# External_Stepper.net
KiCad netlist of a schematic drawn in Altium Designer
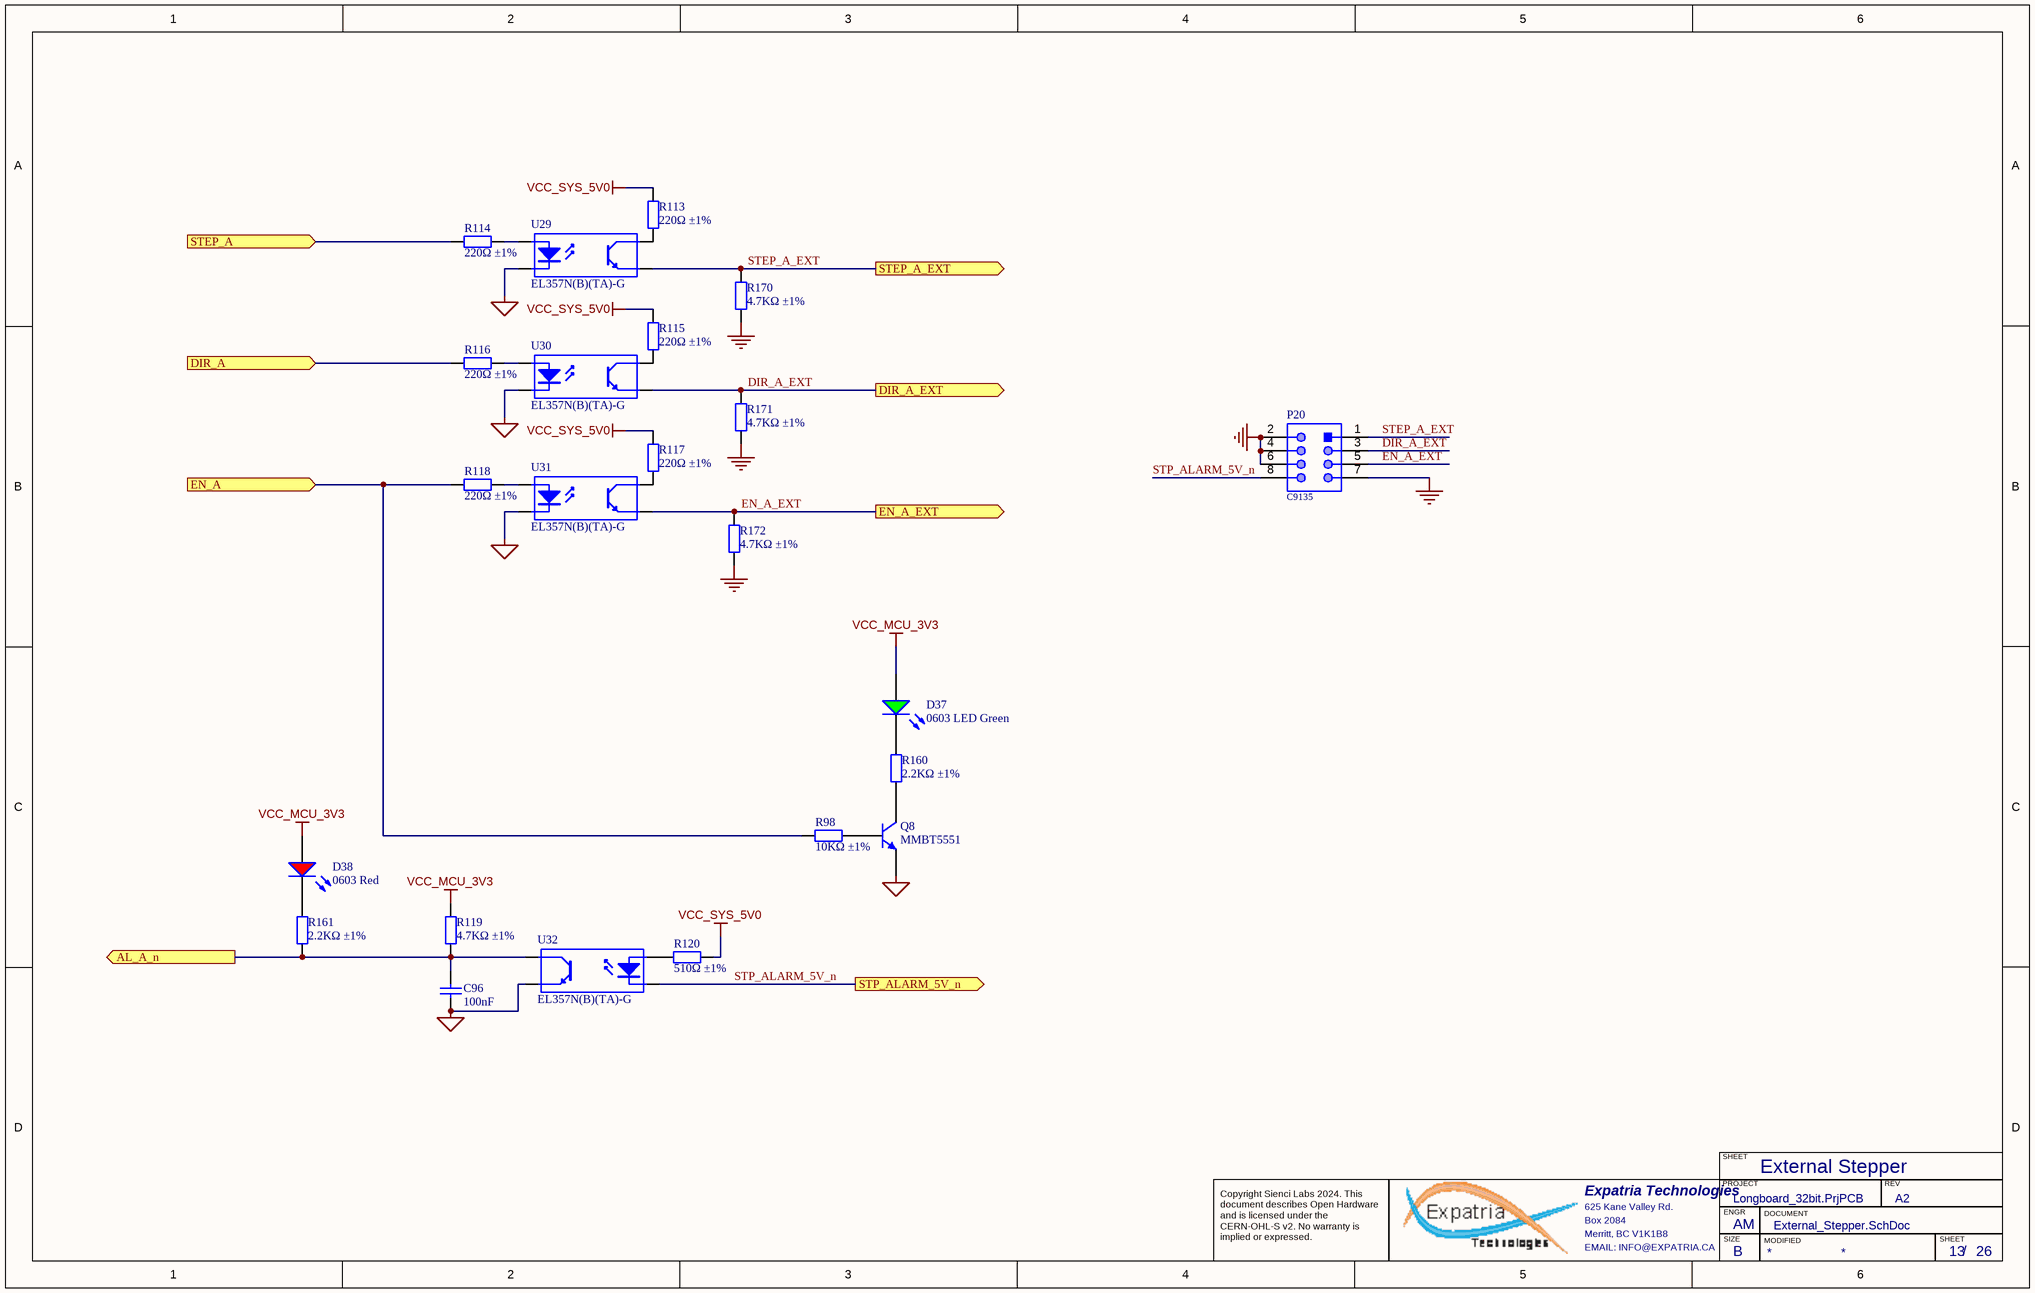
[diagram p0: External_Stepper.SchDoc]

(export (version "E")
  (design (tool "Eeschema 10.0.6"))
  (components
    (comp (ref "C96")
      (value "100nF")
      (footprint "0402_C")
      (description "16V 100nF X7R ±10% 0402 Multilayer Ceramic Capacitors MLCC - SMD/SMT ROHS")
      (fields (field (name "MANUFACTURER") "Samsung Electro-Mechanics") (field (name "TOLERANCE") "10%"))
      (libsource (lib "Sienci_Labs") (part "0402 100nF (104) 10% 16V"))
    )
    (comp (ref "D37")
      (value "0603 LED Green")
      (footprint "0603_LED_S1 - GREEN")
      (fields
        (field (name "MANUFACTURER PART NUMBER") "19-217/GHC-YR1S2/3T")
        (field (name "MANUFACTURER") "Everlight Elec")
      )
      (libsource (lib "Sienci_Labs") (part "19-217/GHC-YR1S2/3T"))
    )
    (comp (ref "D38")
      (value "0603 Red")
      (footprint "0603_LED_S1")
      (fields
        (field (name "MANUFACTURER") "Everlight Elec")
        (field (name "MANUFACTURER PART NUMBER") "19-213SURC/S530-A3/TR8")
      )
      (libsource (lib "Sienci_Labs") (part "19-213SURC/S530-A3/TR8"))
    )
    (comp (ref "P20")
      (value "C9135")
      (footprint "61200821621")
      (description "Male Box Header WR-BHD, THT, Vertical, pitch 2.54 mm, 8 pins")
      (fields
        (field (name "MANUFACTURER") "Wurth Electronics")
        (field (name "MANUFACTURER PART NUMBER") "61200821621")
        (field (name "PUBLISHER") "WurthElektronik")
      )
      (libsource (lib "Sienci_Labs") (part "HDR2x4P"))
    )
    (comp (ref "Q8")
      (value "MMBT5551")
      (footprint "SOT-23(SOT-23-3)")
      (fields (field (name "MANUFACTURER") "Jiangsu Changjing Electronics Technology"))
      (libsource (lib "Sienci_Labs") (part "MMBT5551"))
    )
    (comp (ref "R98")
      (value "10KΩ ±1%")
      (footprint "0603_R")
      (description "Chip resistor")
      (fields
        (field (name "MANUFACTURER") "Uniroyal Elec")
        (field (name "MANUFACTURER PART NUMBER") "0603WAF1002T5E")
      )
      (libsource (lib "RES") (part "0603 10K (1002) 1%"))
    )
    (comp (ref "R113")
      (value "220Ω ±1%")
      (footprint "0402_R")
      (description "Chip resistor")
      (fields
        (field (name "MANUFACTURER") "Uniroyal Elec")
        (field (name "MANUFACTURER PART NUMBER") "0402WGF2200TCE")
      )
      (libsource (lib "") (part "0402 220R (2200) 1%_1"))
    )
    (comp (ref "R114")
      (value "220Ω ±1%")
      (footprint "0402_R")
      (description "Chip resistor")
      (fields
        (field (name "MANUFACTURER") "Uniroyal Elec")
        (field (name "MANUFACTURER PART NUMBER") "0402WGF2200TCE")
      )
      (libsource (lib "RES") (part "0402 220R (2200) 1%"))
    )
    (comp (ref "R115")
      (value "220Ω ±1%")
      (footprint "0402_R")
      (description "Chip resistor")
      (fields
        (field (name "MANUFACTURER") "Uniroyal Elec")
        (field (name "MANUFACTURER PART NUMBER") "0402WGF2200TCE")
      )
      (libsource (lib "") (part "0402 220R (2200) 1%_1"))
    )
    (comp (ref "R116")
      (value "220Ω ±1%")
      (footprint "0402_R")
      (description "Chip resistor")
      (fields
        (field (name "MANUFACTURER") "Uniroyal Elec")
        (field (name "MANUFACTURER PART NUMBER") "0402WGF2200TCE")
      )
      (libsource (lib "RES") (part "0402 220R (2200) 1%"))
    )
    (comp (ref "R117")
      (value "220Ω ±1%")
      (footprint "0402_R")
      (description "Chip resistor")
      (fields
        (field (name "MANUFACTURER") "Uniroyal Elec")
        (field (name "MANUFACTURER PART NUMBER") "0402WGF2200TCE")
      )
      (libsource (lib "") (part "0402 220R (2200) 1%_1"))
    )
    (comp (ref "R118")
      (value "220Ω ±1%")
      (footprint "0402_R")
      (description "Chip resistor")
      (fields
        (field (name "MANUFACTURER") "Uniroyal Elec")
        (field (name "MANUFACTURER PART NUMBER") "0402WGF2200TCE")
      )
      (libsource (lib "RES") (part "0402 220R (2200) 1%"))
    )
    (comp (ref "R119")
      (value "4.7KΩ ±1%")
      (footprint "0402_R")
      (description "Chip resistor")
      (fields
        (field (name "MANUFACTURER") "Uniroyal Elec")
        (field (name "MANUFACTURER PART NUMBER") "0402WGF4701TCE")
      )
      (libsource (lib "") (part "0402 4.7K (4701) 1%_1"))
    )
    (comp (ref "R120")
      (value "510Ω ±1%")
      (footprint "0402_R")
      (description "Chip resistor")
      (fields
        (field (name "MANUFACTURER") "Uniroyal Elec")
        (field (name "MANUFACTURER PART NUMBER") "0402WGF5100TCE")
      )
      (libsource (lib "RES") (part "0402 510R (5100) 1%"))
    )
    (comp (ref "R160")
      (value "2.2KΩ ±1%")
      (footprint "0402_R")
      (description "Chip resistor")
      (fields
        (field (name "MANUFACTURER") "Uniroyal Elec")
        (field (name "MANUFACTURER PART NUMBER") "0402WGF2201TCE")
      )
      (libsource (lib "RES") (part "0402 2.2K (2201) 1%"))
    )
    (comp (ref "R161")
      (value "2.2KΩ ±1%")
      (footprint "0402_R")
      (description "Chip resistor")
      (fields
        (field (name "MANUFACTURER") "Uniroyal Elec")
        (field (name "MANUFACTURER PART NUMBER") "0402WGF2201TCE")
      )
      (libsource (lib "RES") (part "0402 2.2K (2201) 1%"))
    )
    (comp (ref "R170")
      (value "4.7KΩ ±1%")
      (footprint "0402_R")
      (description "Chip resistor")
      (fields
        (field (name "MANUFACTURER") "Uniroyal Elec")
        (field (name "MANUFACTURER PART NUMBER") "0402WGF4701TCE")
      )
      (libsource (lib "RES") (part "0402 4.7K (4701) 1%"))
    )
    (comp (ref "R171")
      (value "4.7KΩ ±1%")
      (footprint "0402_R")
      (description "Chip resistor")
      (fields
        (field (name "MANUFACTURER") "Uniroyal Elec")
        (field (name "MANUFACTURER PART NUMBER") "0402WGF4701TCE")
      )
      (libsource (lib "RES") (part "0402 4.7K (4701) 1%"))
    )
    (comp (ref "R172")
      (value "4.7KΩ ±1%")
      (footprint "0402_R")
      (description "Chip resistor")
      (fields
        (field (name "MANUFACTURER") "Uniroyal Elec")
        (field (name "MANUFACTURER PART NUMBER") "0402WGF4701TCE")
      )
      (libsource (lib "RES") (part "0402 4.7K (4701) 1%"))
    )
    (comp (ref "U29")
      (value "EL357N(B)(TA)-G")
      (footprint "Miscellaneous Devices LC:SOP-4_P2.54")
      (description "80V 3750V 50mA 0.1V@1mA,20mA 1 6V 1.2V DC SOP-4-2.54mm Optocouplers - Phototransistor Output ROHS")
      (fields (field (name "MANUFACTURER") "Everlight Elec"))
      (libsource (lib "IC") (part "EL357N(B)(TA)-G_[C6649]"))
    )
    (comp (ref "U30")
      (value "EL357N(B)(TA)-G")
      (footprint "Miscellaneous Devices LC:SOP-4_P2.54")
      (description "80V 3750V 50mA 0.1V@1mA,20mA 1 6V 1.2V DC SOP-4-2.54mm Optocouplers - Phototransistor Output ROHS")
      (fields (field (name "MANUFACTURER") "Everlight Elec"))
      (libsource (lib "IC") (part "EL357N(B)(TA)-G_[C6649]"))
    )
    (comp (ref "U31")
      (value "EL357N(B)(TA)-G")
      (footprint "Miscellaneous Devices LC:SOP-4_P2.54")
      (description "80V 3750V 50mA 0.1V@1mA,20mA 1 6V 1.2V DC SOP-4-2.54mm Optocouplers - Phototransistor Output ROHS")
      (fields (field (name "MANUFACTURER") "Everlight Elec"))
      (libsource (lib "IC") (part "EL357N(B)(TA)-G_[C6649]"))
    )
    (comp (ref "U32")
      (value "EL357N(B)(TA)-G")
      (footprint "Miscellaneous Devices LC:SOP-4_P2.54")
      (description "80V 3750V 50mA 0.1V@1mA,20mA 1 6V 1.2V DC SOP-4-2.54mm Optocouplers - Phototransistor Output ROHS")
      (fields (field (name "MANUFACTURER") "Everlight Elec"))
      (libsource (lib "IC") (part "EL357N(B)(TA)-G_[C6649]"))
    )
  )
  (nets
    (net (code "1") (name "/AL_A_n") (class "Default")
      (node (ref "C96") (pin "2") (pinfunction "2_2") (pintype "passive"))
      (node (ref "R119") (pin "1") (pinfunction "1_1") (pintype "passive"))
      (node (ref "R161") (pin "1") (pinfunction "1_1") (pintype "passive"))
      (node (ref "U32") (pin "4") (pinfunction "C_4") (pintype "passive"))
    )
    (net (code "2") (name "/DIR_A") (class "Default")
      (node (ref "R116") (pin "1") (pinfunction "1_1") (pintype "passive"))
    )
    (net (code "3") (name "/DIR_A_EXT") (class "Default")
      (node (ref "P20") (pin "3") (pinfunction "3_3") (pintype "passive"))
      (node (ref "R171") (pin "1") (pinfunction "1_1") (pintype "passive"))
      (node (ref "U30") (pin "3") (pinfunction "E_3") (pintype "passive"))
    )
    (net (code "4") (name "/EN_A") (class "Default")
      (node (ref "R118") (pin "1") (pinfunction "1_1") (pintype "passive"))
      (node (ref "R98") (pin "2") (pinfunction "2_2") (pintype "passive"))
    )
    (net (code "5") (name "/EN_A_EXT") (class "Default")
      (node (ref "P20") (pin "5") (pinfunction "5_5") (pintype "passive"))
      (node (ref "R172") (pin "1") (pinfunction "1_1") (pintype "passive"))
      (node (ref "U31") (pin "3") (pinfunction "E_3") (pintype "passive"))
    )
    (net (code "6") (name "/STEP_A") (class "Default")
      (node (ref "R114") (pin "1") (pinfunction "1_1") (pintype "passive"))
    )
    (net (code "7") (name "/STEP_A_EXT") (class "Default")
      (node (ref "P20") (pin "1") (pinfunction "1_1") (pintype "passive"))
      (node (ref "R170") (pin "1") (pinfunction "1_1") (pintype "passive"))
      (node (ref "U29") (pin "3") (pinfunction "E_3") (pintype "passive"))
    )
    (net (code "8") (name "/STP_ALARM_5V_n") (class "Default")
      (node (ref "P20") (pin "8") (pinfunction "8_8") (pintype "passive"))
      (node (ref "U32") (pin "2") (pinfunction "K_2") (pintype "passive"))
    )
    (net (code "9") (name "GND") (class "Default")
      (node (ref "P20") (pin "2") (pinfunction "2_2") (pintype "passive"))
      (node (ref "P20") (pin "4") (pinfunction "4_4") (pintype "passive"))
      (node (ref "P20") (pin "6") (pinfunction "6_6") (pintype "passive"))
      (node (ref "P20") (pin "7") (pinfunction "7_7") (pintype "passive"))
      (node (ref "R170") (pin "2") (pinfunction "2_2") (pintype "passive"))
      (node (ref "R171") (pin "2") (pinfunction "2_2") (pintype "passive"))
      (node (ref "R172") (pin "2") (pinfunction "2_2") (pintype "passive"))
    )
    (net (code "10") (name "MCU_GND") (class "Default")
      (node (ref "C96") (pin "1") (pinfunction "1_1") (pintype "passive"))
      (node (ref "Q8") (pin "2") (pinfunction "E_2") (pintype "passive"))
      (node (ref "U29") (pin "2") (pinfunction "K_2") (pintype "passive"))
      (node (ref "U30") (pin "2") (pinfunction "K_2") (pintype "passive"))
      (node (ref "U31") (pin "2") (pinfunction "K_2") (pintype "passive"))
      (node (ref "U32") (pin "3") (pinfunction "E_3") (pintype "passive"))
    )
    (net (code "11") (name "Net-(D37-PadK)") (class "Default")
      (node (ref "D37") (pin "K") (pinfunction "K_K") (pintype "passive"))
      (node (ref "R160") (pin "2") (pinfunction "2_2") (pintype "passive"))
    )
    (net (code "12") (name "Net-(D38-PadK)") (class "Default")
      (node (ref "D38") (pin "K") (pinfunction "K_K") (pintype "passive"))
      (node (ref "R161") (pin "2") (pinfunction "2_2") (pintype "passive"))
    )
    (net (code "13") (name "Net-(Q8-B)") (class "Default")
      (node (ref "Q8") (pin "1") (pinfunction "B_1") (pintype "passive"))
      (node (ref "R98") (pin "1") (pinfunction "1_1") (pintype "passive"))
    )
    (net (code "14") (name "Net-(Q8-C)") (class "Default")
      (node (ref "Q8") (pin "3") (pinfunction "C_3") (pintype "passive"))
      (node (ref "R160") (pin "1") (pinfunction "1_1") (pintype "passive"))
    )
    (net (code "15") (name "Net-(U29-A)") (class "Default")
      (node (ref "R114") (pin "2") (pinfunction "2_2") (pintype "passive"))
      (node (ref "U29") (pin "1") (pinfunction "A_1") (pintype "passive"))
    )
    (net (code "16") (name "Net-(U29-C)") (class "Default")
      (node (ref "R113") (pin "2") (pinfunction "2_2") (pintype "passive"))
      (node (ref "U29") (pin "4") (pinfunction "C_4") (pintype "passive"))
    )
    (net (code "17") (name "Net-(U30-A)") (class "Default")
      (node (ref "R116") (pin "2") (pinfunction "2_2") (pintype "passive"))
      (node (ref "U30") (pin "1") (pinfunction "A_1") (pintype "passive"))
    )
    (net (code "18") (name "Net-(U30-C)") (class "Default")
      (node (ref "R115") (pin "2") (pinfunction "2_2") (pintype "passive"))
      (node (ref "U30") (pin "4") (pinfunction "C_4") (pintype "passive"))
    )
    (net (code "19") (name "Net-(U31-A)") (class "Default")
      (node (ref "R118") (pin "2") (pinfunction "2_2") (pintype "passive"))
      (node (ref "U31") (pin "1") (pinfunction "A_1") (pintype "passive"))
    )
    (net (code "20") (name "Net-(U31-C)") (class "Default")
      (node (ref "R117") (pin "2") (pinfunction "2_2") (pintype "passive"))
      (node (ref "U31") (pin "4") (pinfunction "C_4") (pintype "passive"))
    )
    (net (code "21") (name "Net-(U32-A)") (class "Default")
      (node (ref "R120") (pin "1") (pinfunction "1_1") (pintype "passive"))
      (node (ref "U32") (pin "1") (pinfunction "A_1") (pintype "passive"))
    )
    (net (code "22") (name "VCC_MCU_3V3") (class "Default")
      (node (ref "D37") (pin "A") (pinfunction "A_A") (pintype "passive"))
      (node (ref "D38") (pin "A") (pinfunction "A_A") (pintype "passive"))
      (node (ref "R119") (pin "2") (pinfunction "2_2") (pintype "passive"))
    )
    (net (code "23") (name "VCC_SYS_5V0") (class "Default")
      (node (ref "R113") (pin "1") (pinfunction "1_1") (pintype "passive"))
      (node (ref "R115") (pin "1") (pinfunction "1_1") (pintype "passive"))
      (node (ref "R117") (pin "1") (pinfunction "1_1") (pintype "passive"))
      (node (ref "R120") (pin "2") (pinfunction "2_2") (pintype "passive"))
    )
  )
)
